# connect.net
KiCad netlist of a schematic drawn in EasyEDA Pro
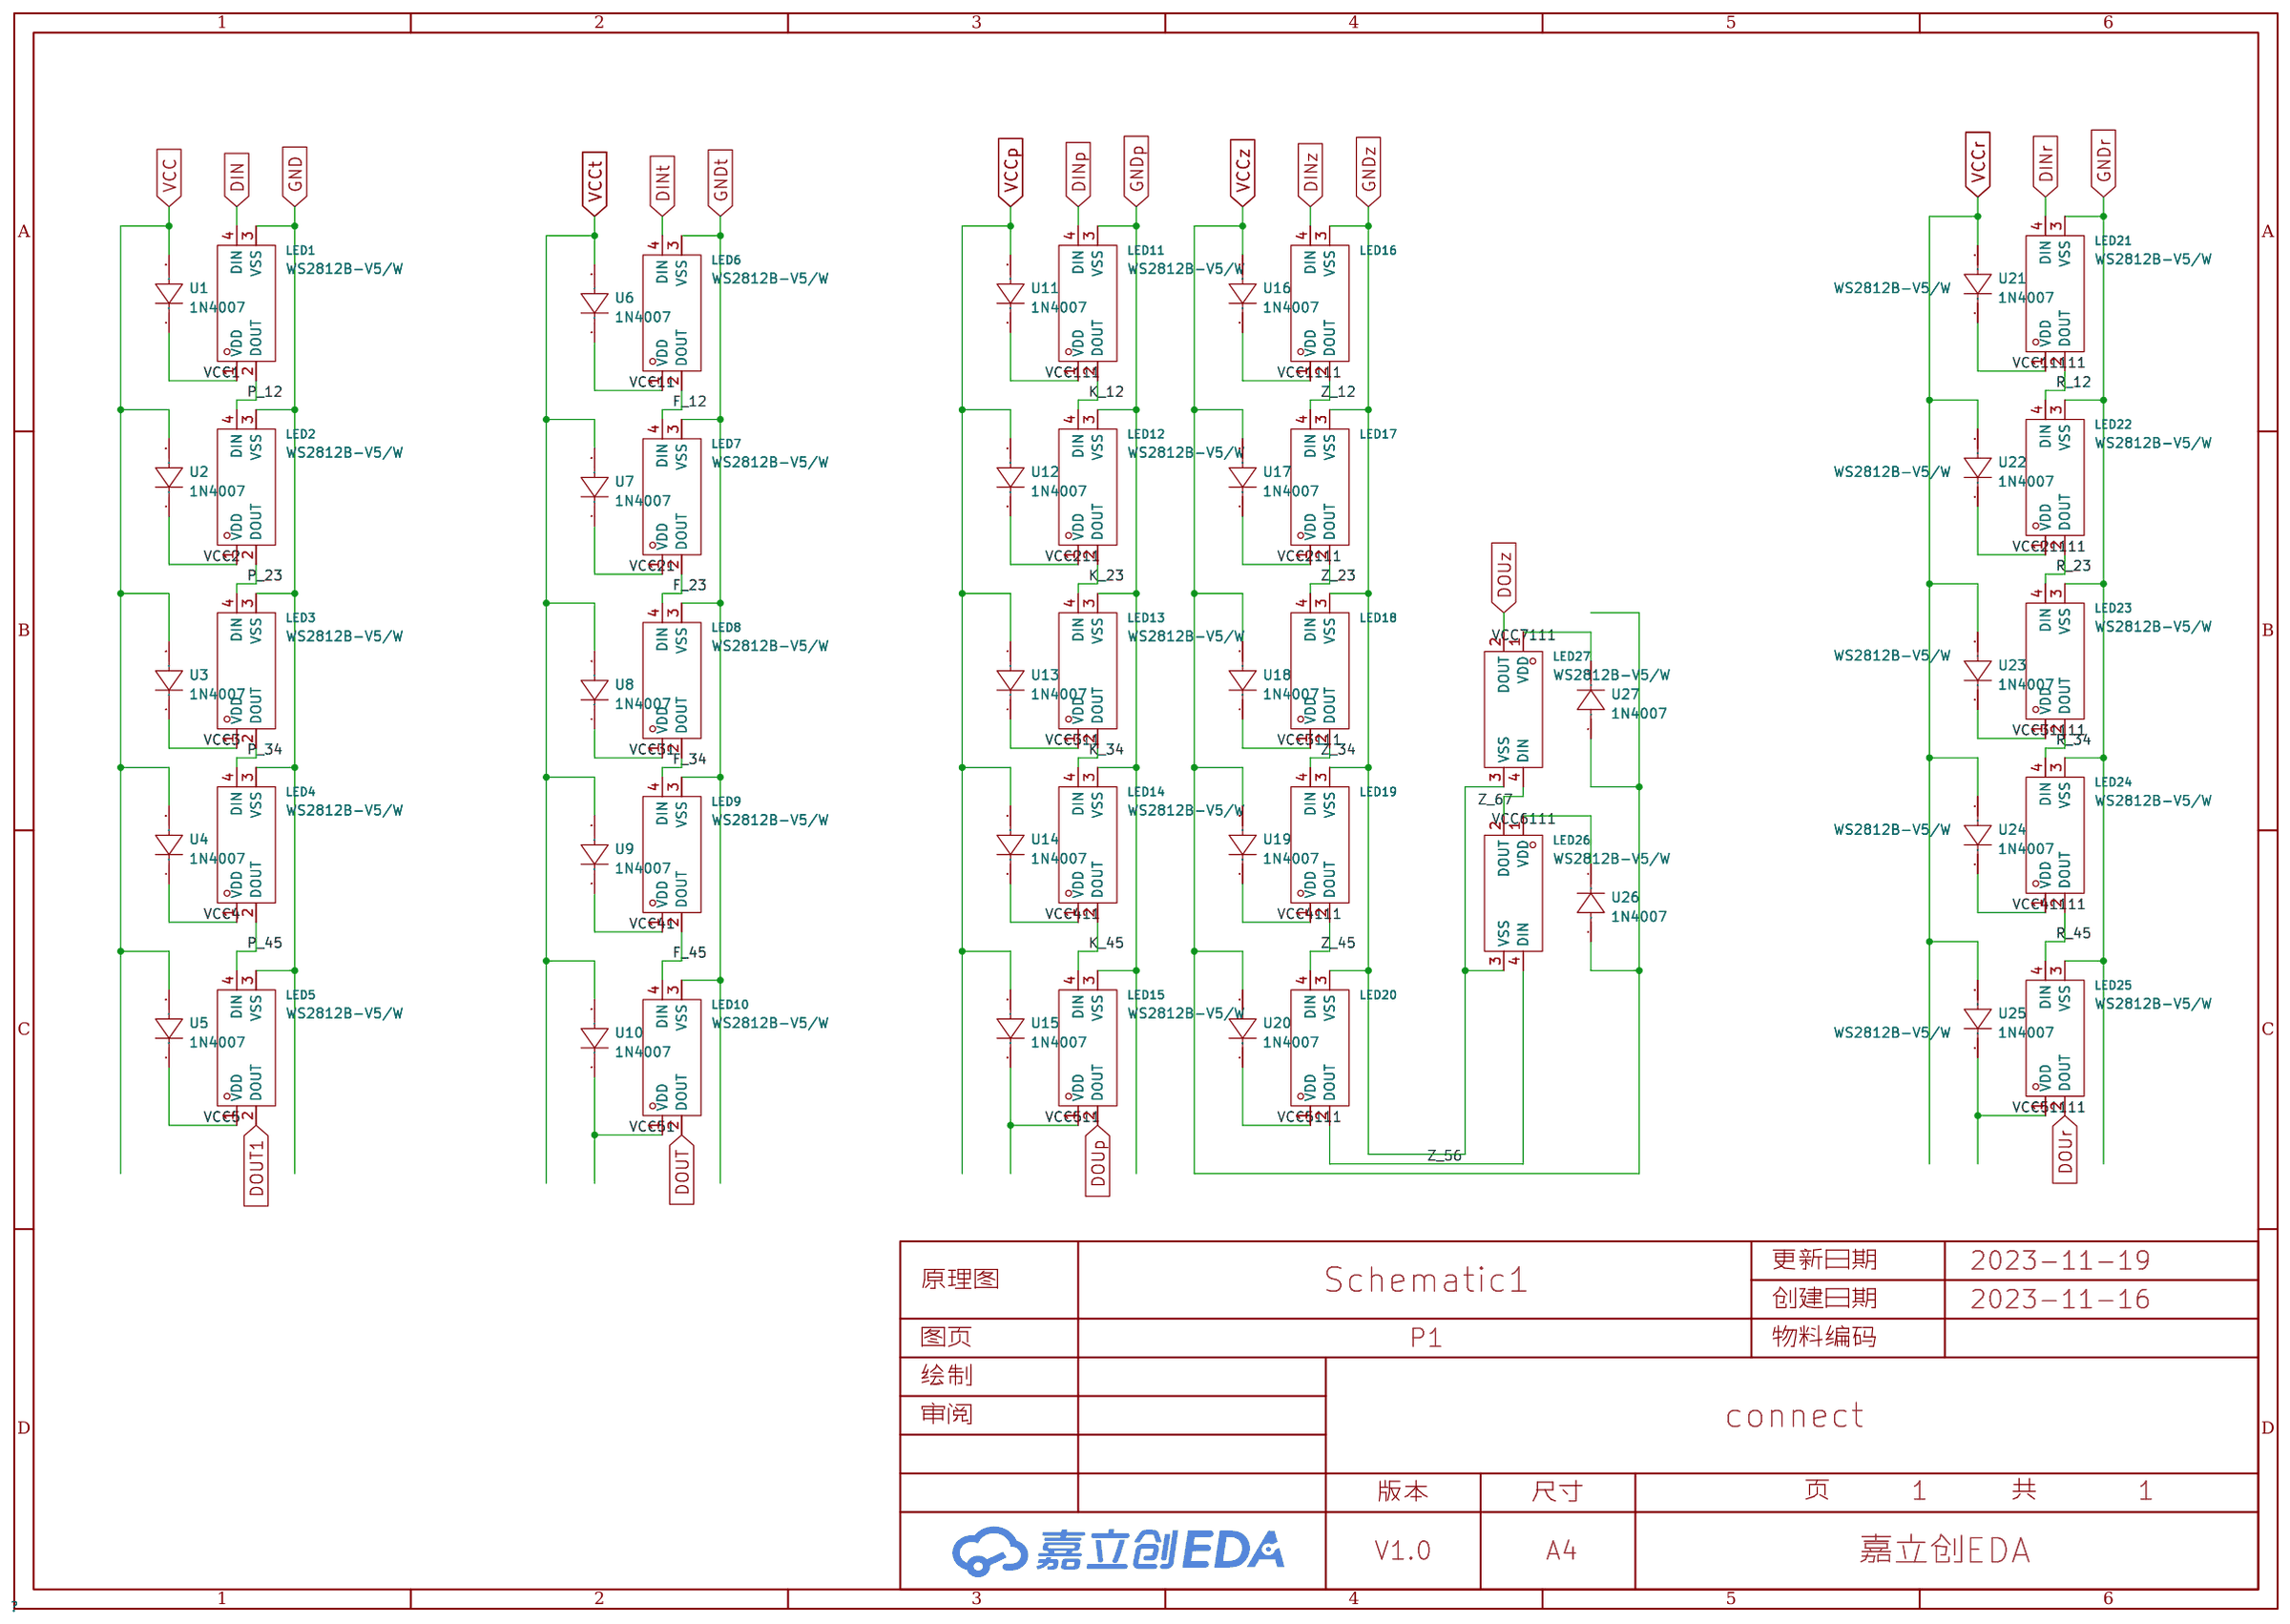
[diagram p0: schematic sheet]

(export (version "E")
  (design (tool "Eeschema 10.0.6"))
  (components
    (comp (ref "LED1")
      (value "WS2812B-V5/W")
      (footprint "easyedapro:LED-SMD_4P-L5.0-W5.0-TL-1")
      (description "无需外围元器件，有反接保护和过压保护，游乐设备，消费类电子，电竞领域，电脑周边及设备")
      (fields (field (name "Manufacturer") "worldsemi"))
      (libsource (lib "easyedapro") (part "WS2812B-V5/W"))
    )
    (comp (ref "LED2")
      (value "WS2812B-V5/W")
      (footprint "easyedapro:LED-SMD_4P-L5.0-W5.0-TL-1")
      (description "无需外围元器件，有反接保护和过压保护，游乐设备，消费类电子，电竞领域，电脑周边及设备")
      (fields (field (name "Manufacturer") "worldsemi"))
      (libsource (lib "easyedapro") (part "WS2812B-V5/W"))
    )
    (comp (ref "LED3")
      (value "WS2812B-V5/W")
      (footprint "easyedapro:LED-SMD_4P-L5.0-W5.0-TL-1")
      (description "无需外围元器件，有反接保护和过压保护，游乐设备，消费类电子，电竞领域，电脑周边及设备")
      (fields (field (name "Manufacturer") "worldsemi"))
      (libsource (lib "easyedapro") (part "WS2812B-V5/W"))
    )
    (comp (ref "LED4")
      (value "WS2812B-V5/W")
      (footprint "easyedapro:LED-SMD_4P-L5.0-W5.0-TL-1")
      (description "无需外围元器件，有反接保护和过压保护，游乐设备，消费类电子，电竞领域，电脑周边及设备")
      (fields (field (name "Manufacturer") "worldsemi"))
      (libsource (lib "easyedapro") (part "WS2812B-V5/W"))
    )
    (comp (ref "LED5")
      (value "WS2812B-V5/W")
      (footprint "easyedapro:LED-SMD_4P-L5.0-W5.0-TL-1")
      (description "无需外围元器件，有反接保护和过压保护，游乐设备，消费类电子，电竞领域，电脑周边及设备")
      (fields (field (name "Manufacturer") "worldsemi"))
      (libsource (lib "easyedapro") (part "WS2812B-V5/W"))
    )
    (comp (ref "LED6")
      (value "WS2812B-V5/W")
      (footprint "easyedapro:LED-SMD_4P-L5.0-W5.0-TL-1")
      (description "无需外围元器件，有反接保护和过压保护，游乐设备，消费类电子，电竞领域，电脑周边及设备")
      (fields (field (name "Manufacturer") "worldsemi"))
      (libsource (lib "easyedapro") (part "WS2812B-V5/W"))
    )
    (comp (ref "LED7")
      (value "WS2812B-V5/W")
      (footprint "easyedapro:LED-SMD_4P-L5.0-W5.0-TL-1")
      (description "无需外围元器件，有反接保护和过压保护，游乐设备，消费类电子，电竞领域，电脑周边及设备")
      (fields (field (name "Manufacturer") "worldsemi"))
      (libsource (lib "easyedapro") (part "WS2812B-V5/W"))
    )
    (comp (ref "LED8")
      (value "WS2812B-V5/W")
      (footprint "easyedapro:LED-SMD_4P-L5.0-W5.0-TL-1")
      (description "无需外围元器件，有反接保护和过压保护，游乐设备，消费类电子，电竞领域，电脑周边及设备")
      (fields (field (name "Manufacturer") "worldsemi"))
      (libsource (lib "easyedapro") (part "WS2812B-V5/W"))
    )
    (comp (ref "LED9")
      (value "WS2812B-V5/W")
      (footprint "easyedapro:LED-SMD_4P-L5.0-W5.0-TL-1")
      (description "无需外围元器件，有反接保护和过压保护，游乐设备，消费类电子，电竞领域，电脑周边及设备")
      (fields (field (name "Manufacturer") "worldsemi"))
      (libsource (lib "easyedapro") (part "WS2812B-V5/W"))
    )
    (comp (ref "LED10")
      (value "WS2812B-V5/W")
      (footprint "easyedapro:LED-SMD_4P-L5.0-W5.0-TL-1")
      (description "无需外围元器件，有反接保护和过压保护，游乐设备，消费类电子，电竞领域，电脑周边及设备")
      (fields (field (name "Manufacturer") "worldsemi"))
      (libsource (lib "easyedapro") (part "WS2812B-V5/W"))
    )
    (comp (ref "LED11")
      (value "WS2812B-V5/W")
      (footprint "easyedapro:LED-SMD_4P-L5.0-W5.0-TL-1")
      (description "无需外围元器件，有反接保护和过压保护，游乐设备，消费类电子，电竞领域，电脑周边及设备")
      (fields (field (name "Manufacturer") "worldsemi"))
      (libsource (lib "easyedapro") (part "WS2812B-V5/W"))
    )
    (comp (ref "LED12")
      (value "WS2812B-V5/W")
      (footprint "easyedapro:LED-SMD_4P-L5.0-W5.0-TL-1")
      (description "无需外围元器件，有反接保护和过压保护，游乐设备，消费类电子，电竞领域，电脑周边及设备")
      (fields (field (name "Manufacturer") "worldsemi"))
      (libsource (lib "easyedapro") (part "WS2812B-V5/W"))
    )
    (comp (ref "LED13")
      (value "WS2812B-V5/W")
      (footprint "easyedapro:LED-SMD_4P-L5.0-W5.0-TL-1")
      (description "无需外围元器件，有反接保护和过压保护，游乐设备，消费类电子，电竞领域，电脑周边及设备")
      (fields (field (name "Manufacturer") "worldsemi"))
      (libsource (lib "easyedapro") (part "WS2812B-V5/W"))
    )
    (comp (ref "LED14")
      (value "WS2812B-V5/W")
      (footprint "easyedapro:LED-SMD_4P-L5.0-W5.0-TL-1")
      (description "无需外围元器件，有反接保护和过压保护，游乐设备，消费类电子，电竞领域，电脑周边及设备")
      (fields (field (name "Manufacturer") "worldsemi"))
      (libsource (lib "easyedapro") (part "WS2812B-V5/W"))
    )
    (comp (ref "LED15")
      (value "WS2812B-V5/W")
      (footprint "easyedapro:LED-SMD_4P-L5.0-W5.0-TL-1")
      (description "无需外围元器件，有反接保护和过压保护，游乐设备，消费类电子，电竞领域，电脑周边及设备")
      (fields (field (name "Manufacturer") "worldsemi"))
      (libsource (lib "easyedapro") (part "WS2812B-V5/W"))
    )
    (comp (ref "LED16")
      (value "WS2812B-V5/W")
      (footprint "easyedapro:LED-SMD_4P-L5.0-W5.0-TL-1")
      (description "无需外围元器件，有反接保护和过压保护，游乐设备，消费类电子，电竞领域，电脑周边及设备")
      (fields (field (name "Manufacturer") "worldsemi"))
      (libsource (lib "easyedapro") (part "WS2812B-V5/W"))
    )
    (comp (ref "LED17")
      (value "WS2812B-V5/W")
      (footprint "easyedapro:LED-SMD_4P-L5.0-W5.0-TL-1")
      (description "无需外围元器件，有反接保护和过压保护，游乐设备，消费类电子，电竞领域，电脑周边及设备")
      (fields (field (name "Manufacturer") "worldsemi"))
      (libsource (lib "easyedapro") (part "WS2812B-V5/W"))
    )
    (comp (ref "LED18")
      (value "WS2812B-V5/W")
      (footprint "easyedapro:LED-SMD_4P-L5.0-W5.0-TL-1")
      (description "无需外围元器件，有反接保护和过压保护，游乐设备，消费类电子，电竞领域，电脑周边及设备")
      (fields (field (name "Manufacturer") "worldsemi"))
      (libsource (lib "easyedapro") (part "WS2812B-V5/W"))
    )
    (comp (ref "LED19")
      (value "WS2812B-V5/W")
      (footprint "easyedapro:LED-SMD_4P-L5.0-W5.0-TL-1")
      (description "无需外围元器件，有反接保护和过压保护，游乐设备，消费类电子，电竞领域，电脑周边及设备")
      (fields (field (name "Manufacturer") "worldsemi"))
      (libsource (lib "easyedapro") (part "WS2812B-V5/W"))
    )
    (comp (ref "LED20")
      (value "WS2812B-V5/W")
      (footprint "easyedapro:LED-SMD_4P-L5.0-W5.0-TL-1")
      (description "无需外围元器件，有反接保护和过压保护，游乐设备，消费类电子，电竞领域，电脑周边及设备")
      (fields (field (name "Manufacturer") "worldsemi"))
      (libsource (lib "easyedapro") (part "WS2812B-V5/W"))
    )
    (comp (ref "LED21")
      (value "WS2812B-V5/W")
      (footprint "easyedapro:LED-SMD_4P-L5.0-W5.0-TL-1")
      (description "无需外围元器件，有反接保护和过压保护，游乐设备，消费类电子，电竞领域，电脑周边及设备")
      (fields (field (name "Manufacturer") "worldsemi"))
      (libsource (lib "easyedapro") (part "WS2812B-V5/W"))
    )
    (comp (ref "LED22")
      (value "WS2812B-V5/W")
      (footprint "easyedapro:LED-SMD_4P-L5.0-W5.0-TL-1")
      (description "无需外围元器件，有反接保护和过压保护，游乐设备，消费类电子，电竞领域，电脑周边及设备")
      (fields (field (name "Manufacturer") "worldsemi"))
      (libsource (lib "easyedapro") (part "WS2812B-V5/W"))
    )
    (comp (ref "LED23")
      (value "WS2812B-V5/W")
      (footprint "easyedapro:LED-SMD_4P-L5.0-W5.0-TL-1")
      (description "无需外围元器件，有反接保护和过压保护，游乐设备，消费类电子，电竞领域，电脑周边及设备")
      (fields (field (name "Manufacturer") "worldsemi"))
      (libsource (lib "easyedapro") (part "WS2812B-V5/W"))
    )
    (comp (ref "LED24")
      (value "WS2812B-V5/W")
      (footprint "easyedapro:LED-SMD_4P-L5.0-W5.0-TL-1")
      (description "无需外围元器件，有反接保护和过压保护，游乐设备，消费类电子，电竞领域，电脑周边及设备")
      (fields (field (name "Manufacturer") "worldsemi"))
      (libsource (lib "easyedapro") (part "WS2812B-V5/W"))
    )
    (comp (ref "LED25")
      (value "WS2812B-V5/W")
      (footprint "easyedapro:LED-SMD_4P-L5.0-W5.0-TL-1")
      (description "无需外围元器件，有反接保护和过压保护，游乐设备，消费类电子，电竞领域，电脑周边及设备")
      (fields (field (name "Manufacturer") "worldsemi"))
      (libsource (lib "easyedapro") (part "WS2812B-V5/W"))
    )
    (comp (ref "LED26")
      (value "WS2812B-V5/W")
      (footprint "easyedapro:LED-SMD_4P-L5.0-W5.0-TL-1")
      (description "无需外围元器件，有反接保护和过压保护，游乐设备，消费类电子，电竞领域，电脑周边及设备")
      (fields (field (name "Manufacturer") "worldsemi"))
      (libsource (lib "easyedapro") (part "WS2812B-V5/W"))
    )
    (comp (ref "LED27")
      (value "WS2812B-V5/W")
      (footprint "easyedapro:LED-SMD_4P-L5.0-W5.0-TL-1")
      (description "无需外围元器件，有反接保护和过压保护，游乐设备，消费类电子，电竞领域，电脑周边及设备")
      (fields (field (name "Manufacturer") "worldsemi"))
      (libsource (lib "easyedapro") (part "WS2812B-V5/W"))
    )
    (comp (ref "U1")
      (value "1N4007")
      (footprint "easyedapro:SMA_L4.3-W2.6-LS5.1-RD")
      (libsource (lib "easyedapro") (part "1N4007_C9900004759"))
    )
    (comp (ref "U2")
      (value "1N4007")
      (footprint "easyedapro:SMA_L4.3-W2.6-LS5.1-RD")
      (libsource (lib "easyedapro") (part "1N4007_C9900004759"))
    )
    (comp (ref "U3")
      (value "1N4007")
      (footprint "easyedapro:SMA_L4.3-W2.6-LS5.1-RD")
      (libsource (lib "easyedapro") (part "1N4007_C9900004759"))
    )
    (comp (ref "U4")
      (value "1N4007")
      (footprint "easyedapro:SMA_L4.3-W2.6-LS5.1-RD")
      (libsource (lib "easyedapro") (part "1N4007_C9900004759"))
    )
    (comp (ref "U5")
      (value "1N4007")
      (footprint "easyedapro:SMA_L4.3-W2.6-LS5.1-RD")
      (libsource (lib "easyedapro") (part "1N4007_C9900004759"))
    )
    (comp (ref "U6")
      (value "1N4007")
      (footprint "easyedapro:SMA_L4.3-W2.6-LS5.1-RD")
      (libsource (lib "easyedapro") (part "1N4007_C9900004759"))
    )
    (comp (ref "U7")
      (value "1N4007")
      (footprint "easyedapro:SMA_L4.3-W2.6-LS5.1-RD")
      (libsource (lib "easyedapro") (part "1N4007_C9900004759"))
    )
    (comp (ref "U8")
      (value "1N4007")
      (footprint "easyedapro:SMA_L4.3-W2.6-LS5.1-RD")
      (libsource (lib "easyedapro") (part "1N4007_C9900004759"))
    )
    (comp (ref "U9")
      (value "1N4007")
      (footprint "easyedapro:SMA_L4.3-W2.6-LS5.1-RD")
      (libsource (lib "easyedapro") (part "1N4007_C9900004759"))
    )
    (comp (ref "U10")
      (value "1N4007")
      (footprint "easyedapro:SMA_L4.3-W2.6-LS5.1-RD")
      (libsource (lib "easyedapro") (part "1N4007_C9900004759"))
    )
    (comp (ref "U11")
      (value "1N4007")
      (footprint "easyedapro:SMA_L4.3-W2.6-LS5.1-RD")
      (libsource (lib "easyedapro") (part "1N4007_C9900004759"))
    )
    (comp (ref "U12")
      (value "1N4007")
      (footprint "easyedapro:SMA_L4.3-W2.6-LS5.1-RD")
      (libsource (lib "easyedapro") (part "1N4007_C9900004759"))
    )
    (comp (ref "U13")
      (value "1N4007")
      (footprint "easyedapro:SMA_L4.3-W2.6-LS5.1-RD")
      (libsource (lib "easyedapro") (part "1N4007_C9900004759"))
    )
    (comp (ref "U14")
      (value "1N4007")
      (footprint "easyedapro:SMA_L4.3-W2.6-LS5.1-RD")
      (libsource (lib "easyedapro") (part "1N4007_C9900004759"))
    )
    (comp (ref "U15")
      (value "1N4007")
      (footprint "easyedapro:SMA_L4.3-W2.6-LS5.1-RD")
      (libsource (lib "easyedapro") (part "1N4007_C9900004759"))
    )
    (comp (ref "U16")
      (value "1N4007")
      (footprint "easyedapro:SMA_L4.3-W2.6-LS5.1-RD")
      (libsource (lib "easyedapro") (part "1N4007_C9900004759"))
    )
    (comp (ref "U17")
      (value "1N4007")
      (footprint "easyedapro:SMA_L4.3-W2.6-LS5.1-RD")
      (libsource (lib "easyedapro") (part "1N4007_C9900004759"))
    )
    (comp (ref "U18")
      (value "1N4007")
      (footprint "easyedapro:SMA_L4.3-W2.6-LS5.1-RD")
      (libsource (lib "easyedapro") (part "1N4007_C9900004759"))
    )
    (comp (ref "U19")
      (value "1N4007")
      (footprint "easyedapro:SMA_L4.3-W2.6-LS5.1-RD")
      (libsource (lib "easyedapro") (part "1N4007_C9900004759"))
    )
    (comp (ref "U20")
      (value "1N4007")
      (footprint "easyedapro:SMA_L4.3-W2.6-LS5.1-RD")
      (libsource (lib "easyedapro") (part "1N4007_C9900004759"))
    )
    (comp (ref "U21")
      (value "1N4007")
      (footprint "easyedapro:SMA_L4.3-W2.6-LS5.1-RD")
      (libsource (lib "easyedapro") (part "1N4007_C9900004759"))
    )
    (comp (ref "U22")
      (value "1N4007")
      (footprint "easyedapro:SMA_L4.3-W2.6-LS5.1-RD")
      (libsource (lib "easyedapro") (part "1N4007_C9900004759"))
    )
    (comp (ref "U23")
      (value "1N4007")
      (footprint "easyedapro:SMA_L4.3-W2.6-LS5.1-RD")
      (libsource (lib "easyedapro") (part "1N4007_C9900004759"))
    )
    (comp (ref "U24")
      (value "1N4007")
      (footprint "easyedapro:SMA_L4.3-W2.6-LS5.1-RD")
      (libsource (lib "easyedapro") (part "1N4007_C9900004759"))
    )
    (comp (ref "U25")
      (value "1N4007")
      (footprint "easyedapro:SMA_L4.3-W2.6-LS5.1-RD")
      (libsource (lib "easyedapro") (part "1N4007_C9900004759"))
    )
    (comp (ref "U26")
      (value "1N4007")
      (footprint "easyedapro:SMA_L4.3-W2.6-LS5.1-RD")
      (libsource (lib "easyedapro") (part "1N4007_C9900004759"))
    )
    (comp (ref "U27")
      (value "1N4007")
      (footprint "easyedapro:SMA_L4.3-W2.6-LS5.1-RD")
      (libsource (lib "easyedapro") (part "1N4007_C9900004759"))
    )
  )
  (nets
    (net (code "1") (name "/F_12") (class "Default")
      (node (ref "LED6") (pin "2") (pinfunction "DOUT_2") (pintype "input"))
      (node (ref "LED7") (pin "4") (pinfunction "DIN_4") (pintype "input"))
    )
    (net (code "2") (name "/F_23") (class "Default")
      (node (ref "LED7") (pin "2") (pinfunction "DOUT_2") (pintype "input"))
      (node (ref "LED8") (pin "4") (pinfunction "DIN_4") (pintype "input"))
    )
    (net (code "3") (name "/F_34") (class "Default")
      (node (ref "LED8") (pin "2") (pinfunction "DOUT_2") (pintype "input"))
      (node (ref "LED9") (pin "4") (pinfunction "DIN_4") (pintype "input"))
    )
    (net (code "4") (name "/F_45") (class "Default")
      (node (ref "LED10") (pin "4") (pinfunction "DIN_4") (pintype "input"))
      (node (ref "LED9") (pin "2") (pinfunction "DOUT_2") (pintype "input"))
    )
    (net (code "5") (name "/K_12") (class "Default")
      (node (ref "LED11") (pin "2") (pinfunction "DOUT_2") (pintype "input"))
      (node (ref "LED12") (pin "4") (pinfunction "DIN_4") (pintype "input"))
    )
    (net (code "6") (name "/K_23") (class "Default")
      (node (ref "LED12") (pin "2") (pinfunction "DOUT_2") (pintype "input"))
      (node (ref "LED13") (pin "4") (pinfunction "DIN_4") (pintype "input"))
    )
    (net (code "7") (name "/K_34") (class "Default")
      (node (ref "LED13") (pin "2") (pinfunction "DOUT_2") (pintype "input"))
      (node (ref "LED14") (pin "4") (pinfunction "DIN_4") (pintype "input"))
    )
    (net (code "8") (name "/K_45") (class "Default")
      (node (ref "LED14") (pin "2") (pinfunction "DOUT_2") (pintype "input"))
      (node (ref "LED15") (pin "4") (pinfunction "DIN_4") (pintype "input"))
    )
    (net (code "9") (name "/P_12") (class "Default")
      (node (ref "LED1") (pin "2") (pinfunction "DOUT_2") (pintype "input"))
      (node (ref "LED2") (pin "4") (pinfunction "DIN_4") (pintype "input"))
    )
    (net (code "10") (name "/P_23") (class "Default")
      (node (ref "LED2") (pin "2") (pinfunction "DOUT_2") (pintype "input"))
      (node (ref "LED3") (pin "4") (pinfunction "DIN_4") (pintype "input"))
    )
    (net (code "11") (name "/P_34") (class "Default")
      (node (ref "LED3") (pin "2") (pinfunction "DOUT_2") (pintype "input"))
      (node (ref "LED4") (pin "4") (pinfunction "DIN_4") (pintype "input"))
    )
    (net (code "12") (name "/P_45") (class "Default")
      (node (ref "LED4") (pin "2") (pinfunction "DOUT_2") (pintype "input"))
      (node (ref "LED5") (pin "4") (pinfunction "DIN_4") (pintype "input"))
    )
    (net (code "13") (name "/R_12") (class "Default")
      (node (ref "LED21") (pin "2") (pinfunction "DOUT_2") (pintype "input"))
      (node (ref "LED22") (pin "4") (pinfunction "DIN_4") (pintype "input"))
    )
    (net (code "14") (name "/R_23") (class "Default")
      (node (ref "LED22") (pin "2") (pinfunction "DOUT_2") (pintype "input"))
      (node (ref "LED23") (pin "4") (pinfunction "DIN_4") (pintype "input"))
    )
    (net (code "15") (name "/R_34") (class "Default")
      (node (ref "LED23") (pin "2") (pinfunction "DOUT_2") (pintype "input"))
      (node (ref "LED24") (pin "4") (pinfunction "DIN_4") (pintype "input"))
    )
    (net (code "16") (name "/R_45") (class "Default")
      (node (ref "LED24") (pin "2") (pinfunction "DOUT_2") (pintype "input"))
      (node (ref "LED25") (pin "4") (pinfunction "DIN_4") (pintype "input"))
    )
    (net (code "17") (name "/VCC1") (class "Default")
      (node (ref "LED1") (pin "1") (pinfunction "VDD_1") (pintype "input"))
      (node (ref "U1") (pin "1") (pinfunction "K_1") (pintype "input"))
    )
    (net (code "18") (name "/VCC2") (class "Default")
      (node (ref "LED2") (pin "1") (pinfunction "VDD_1") (pintype "input"))
      (node (ref "U2") (pin "1") (pinfunction "K_1") (pintype "input"))
    )
    (net (code "19") (name "/VCC3") (class "Default")
      (node (ref "LED3") (pin "1") (pinfunction "VDD_1") (pintype "input"))
      (node (ref "U3") (pin "1") (pinfunction "K_1") (pintype "input"))
    )
    (net (code "20") (name "/VCC4") (class "Default")
      (node (ref "LED4") (pin "1") (pinfunction "VDD_1") (pintype "input"))
      (node (ref "U4") (pin "1") (pinfunction "K_1") (pintype "input"))
    )
    (net (code "21") (name "/VCC5") (class "Default")
      (node (ref "LED5") (pin "1") (pinfunction "VDD_1") (pintype "input"))
      (node (ref "U5") (pin "1") (pinfunction "K_1") (pintype "input"))
    )
    (net (code "22") (name "/VCC11") (class "Default")
      (node (ref "LED6") (pin "1") (pinfunction "VDD_1") (pintype "input"))
      (node (ref "U6") (pin "1") (pinfunction "K_1") (pintype "input"))
    )
    (net (code "23") (name "/VCC21") (class "Default")
      (node (ref "LED7") (pin "1") (pinfunction "VDD_1") (pintype "input"))
      (node (ref "U7") (pin "1") (pinfunction "K_1") (pintype "input"))
    )
    (net (code "24") (name "/VCC31") (class "Default")
      (node (ref "LED8") (pin "1") (pinfunction "VDD_1") (pintype "input"))
      (node (ref "U8") (pin "1") (pinfunction "K_1") (pintype "input"))
    )
    (net (code "25") (name "/VCC41") (class "Default")
      (node (ref "LED9") (pin "1") (pinfunction "VDD_1") (pintype "input"))
      (node (ref "U9") (pin "1") (pinfunction "K_1") (pintype "input"))
    )
    (net (code "26") (name "/VCC51") (class "Default")
      (node (ref "LED10") (pin "1") (pinfunction "VDD_1") (pintype "input"))
      (node (ref "U10") (pin "1") (pinfunction "K_1") (pintype "input"))
    )
    (net (code "27") (name "/VCC111") (class "Default")
      (node (ref "LED11") (pin "1") (pinfunction "VDD_1") (pintype "input"))
      (node (ref "U11") (pin "1") (pinfunction "K_1") (pintype "input"))
    )
    (net (code "28") (name "/VCC211") (class "Default")
      (node (ref "LED12") (pin "1") (pinfunction "VDD_1") (pintype "input"))
      (node (ref "U12") (pin "1") (pinfunction "K_1") (pintype "input"))
    )
    (net (code "29") (name "/VCC311") (class "Default")
      (node (ref "LED13") (pin "1") (pinfunction "VDD_1") (pintype "input"))
      (node (ref "U13") (pin "1") (pinfunction "K_1") (pintype "input"))
    )
    (net (code "30") (name "/VCC411") (class "Default")
      (node (ref "LED14") (pin "1") (pinfunction "VDD_1") (pintype "input"))
      (node (ref "U14") (pin "1") (pinfunction "K_1") (pintype "input"))
    )
    (net (code "31") (name "/VCC511") (class "Default")
      (node (ref "LED15") (pin "1") (pinfunction "VDD_1") (pintype "input"))
      (node (ref "U15") (pin "1") (pinfunction "K_1") (pintype "input"))
    )
    (net (code "32") (name "/VCC1111") (class "Default")
      (node (ref "LED16") (pin "1") (pinfunction "VDD_1") (pintype "input"))
      (node (ref "U16") (pin "1") (pinfunction "K_1") (pintype "input"))
    )
    (net (code "33") (name "/VCC2111") (class "Default")
      (node (ref "LED17") (pin "1") (pinfunction "VDD_1") (pintype "input"))
      (node (ref "U17") (pin "1") (pinfunction "K_1") (pintype "input"))
    )
    (net (code "34") (name "/VCC3111") (class "Default")
      (node (ref "LED18") (pin "1") (pinfunction "VDD_1") (pintype "input"))
      (node (ref "U18") (pin "1") (pinfunction "K_1") (pintype "input"))
    )
    (net (code "35") (name "/VCC4111") (class "Default")
      (node (ref "LED19") (pin "1") (pinfunction "VDD_1") (pintype "input"))
      (node (ref "U19") (pin "1") (pinfunction "K_1") (pintype "input"))
    )
    (net (code "36") (name "/VCC5111") (class "Default")
      (node (ref "LED20") (pin "1") (pinfunction "VDD_1") (pintype "input"))
      (node (ref "U20") (pin "1") (pinfunction "K_1") (pintype "input"))
    )
    (net (code "37") (name "/VCC6111") (class "Default")
      (node (ref "LED26") (pin "1") (pinfunction "VDD_1") (pintype "input"))
      (node (ref "U26") (pin "1") (pinfunction "K_1") (pintype "input"))
    )
    (net (code "38") (name "/VCC7111") (class "Default")
      (node (ref "LED27") (pin "1") (pinfunction "VDD_1") (pintype "input"))
      (node (ref "U27") (pin "1") (pinfunction "K_1") (pintype "input"))
    )
    (net (code "39") (name "/VCC11111") (class "Default")
      (node (ref "LED21") (pin "1") (pinfunction "VDD_1") (pintype "input"))
      (node (ref "U21") (pin "1") (pinfunction "K_1") (pintype "input"))
    )
    (net (code "40") (name "/VCC21111") (class "Default")
      (node (ref "LED22") (pin "1") (pinfunction "VDD_1") (pintype "input"))
      (node (ref "U22") (pin "1") (pinfunction "K_1") (pintype "input"))
    )
    (net (code "41") (name "/VCC31111") (class "Default")
      (node (ref "LED23") (pin "1") (pinfunction "VDD_1") (pintype "input"))
      (node (ref "U23") (pin "1") (pinfunction "K_1") (pintype "input"))
    )
    (net (code "42") (name "/VCC41111") (class "Default")
      (node (ref "LED24") (pin "1") (pinfunction "VDD_1") (pintype "input"))
      (node (ref "U24") (pin "1") (pinfunction "K_1") (pintype "input"))
    )
    (net (code "43") (name "/VCC51111") (class "Default")
      (node (ref "LED25") (pin "1") (pinfunction "VDD_1") (pintype "input"))
      (node (ref "U25") (pin "1") (pinfunction "K_1") (pintype "input"))
    )
    (net (code "44") (name "/Z_12") (class "Default")
      (node (ref "LED16") (pin "2") (pinfunction "DOUT_2") (pintype "input"))
      (node (ref "LED17") (pin "4") (pinfunction "DIN_4") (pintype "input"))
    )
    (net (code "45") (name "/Z_23") (class "Default")
      (node (ref "LED17") (pin "2") (pinfunction "DOUT_2") (pintype "input"))
      (node (ref "LED18") (pin "4") (pinfunction "DIN_4") (pintype "input"))
    )
    (net (code "46") (name "/Z_34") (class "Default")
      (node (ref "LED18") (pin "2") (pinfunction "DOUT_2") (pintype "input"))
      (node (ref "LED19") (pin "4") (pinfunction "DIN_4") (pintype "input"))
    )
    (net (code "47") (name "/Z_45") (class "Default")
      (node (ref "LED19") (pin "2") (pinfunction "DOUT_2") (pintype "input"))
      (node (ref "LED20") (pin "4") (pinfunction "DIN_4") (pintype "input"))
    )
    (net (code "48") (name "/Z_56") (class "Default")
      (node (ref "LED20") (pin "2") (pinfunction "DOUT_2") (pintype "input"))
      (node (ref "LED26") (pin "4") (pinfunction "DIN_4") (pintype "input"))
    )
    (net (code "49") (name "/Z_67") (class "Default")
      (node (ref "LED26") (pin "2") (pinfunction "DOUT_2") (pintype "input"))
      (node (ref "LED27") (pin "4") (pinfunction "DIN_4") (pintype "input"))
    )
    (net (code "50") (name "DIN") (class "Default")
      (node (ref "LED1") (pin "4") (pinfunction "DIN_4") (pintype "input"))
    )
    (net (code "51") (name "DINp") (class "Default")
      (node (ref "LED11") (pin "4") (pinfunction "DIN_4") (pintype "input"))
    )
    (net (code "52") (name "DINr") (class "Default")
      (node (ref "LED21") (pin "4") (pinfunction "DIN_4") (pintype "input"))
    )
    (net (code "53") (name "DINt") (class "Default")
      (node (ref "LED6") (pin "4") (pinfunction "DIN_4") (pintype "input"))
    )
    (net (code "54") (name "DINz") (class "Default")
      (node (ref "LED16") (pin "4") (pinfunction "DIN_4") (pintype "input"))
    )
    (net (code "55") (name "DOUT") (class "Default")
      (node (ref "LED10") (pin "2") (pinfunction "DOUT_2") (pintype "input"))
    )
    (net (code "56") (name "DOUT1") (class "Default")
      (node (ref "LED5") (pin "2") (pinfunction "DOUT_2") (pintype "input"))
    )
    (net (code "57") (name "DOUp") (class "Default")
      (node (ref "LED15") (pin "2") (pinfunction "DOUT_2") (pintype "input"))
    )
    (net (code "58") (name "DOUr") (class "Default")
      (node (ref "LED25") (pin "2") (pinfunction "DOUT_2") (pintype "input"))
    )
    (net (code "59") (name "DOUz") (class "Default")
      (node (ref "LED27") (pin "2") (pinfunction "DOUT_2") (pintype "input"))
    )
    (net (code "60") (name "GND") (class "Default")
      (node (ref "LED1") (pin "3") (pinfunction "VSS_3") (pintype "input"))
      (node (ref "LED2") (pin "3") (pinfunction "VSS_3") (pintype "input"))
      (node (ref "LED3") (pin "3") (pinfunction "VSS_3") (pintype "input"))
      (node (ref "LED4") (pin "3") (pinfunction "VSS_3") (pintype "input"))
      (node (ref "LED5") (pin "3") (pinfunction "VSS_3") (pintype "input"))
    )
    (net (code "61") (name "GNDp") (class "Default")
      (node (ref "LED11") (pin "3") (pinfunction "VSS_3") (pintype "input"))
      (node (ref "LED12") (pin "3") (pinfunction "VSS_3") (pintype "input"))
      (node (ref "LED13") (pin "3") (pinfunction "VSS_3") (pintype "input"))
      (node (ref "LED14") (pin "3") (pinfunction "VSS_3") (pintype "input"))
      (node (ref "LED15") (pin "3") (pinfunction "VSS_3") (pintype "input"))
    )
    (net (code "62") (name "GNDr") (class "Default")
      (node (ref "LED21") (pin "3") (pinfunction "VSS_3") (pintype "input"))
      (node (ref "LED22") (pin "3") (pinfunction "VSS_3") (pintype "input"))
      (node (ref "LED23") (pin "3") (pinfunction "VSS_3") (pintype "input"))
      (node (ref "LED24") (pin "3") (pinfunction "VSS_3") (pintype "input"))
      (node (ref "LED25") (pin "3") (pinfunction "VSS_3") (pintype "input"))
    )
    (net (code "63") (name "GNDt") (class "Default")
      (node (ref "LED10") (pin "3") (pinfunction "VSS_3") (pintype "input"))
      (node (ref "LED6") (pin "3") (pinfunction "VSS_3") (pintype "input"))
      (node (ref "LED7") (pin "3") (pinfunction "VSS_3") (pintype "input"))
      (node (ref "LED8") (pin "3") (pinfunction "VSS_3") (pintype "input"))
      (node (ref "LED9") (pin "3") (pinfunction "VSS_3") (pintype "input"))
    )
    (net (code "64") (name "GNDz") (class "Default")
      (node (ref "LED16") (pin "3") (pinfunction "VSS_3") (pintype "input"))
      (node (ref "LED17") (pin "3") (pinfunction "VSS_3") (pintype "input"))
      (node (ref "LED18") (pin "3") (pinfunction "VSS_3") (pintype "input"))
      (node (ref "LED19") (pin "3") (pinfunction "VSS_3") (pintype "input"))
      (node (ref "LED20") (pin "3") (pinfunction "VSS_3") (pintype "input"))
      (node (ref "LED26") (pin "3") (pinfunction "VSS_3") (pintype "input"))
      (node (ref "LED27") (pin "3") (pinfunction "VSS_3") (pintype "input"))
    )
    (net (code "65") (name "VCC") (class "Default")
      (node (ref "U1") (pin "2") (pinfunction "A_2") (pintype "input"))
      (node (ref "U2") (pin "2") (pinfunction "A_2") (pintype "input"))
      (node (ref "U3") (pin "2") (pinfunction "A_2") (pintype "input"))
      (node (ref "U4") (pin "2") (pinfunction "A_2") (pintype "input"))
      (node (ref "U5") (pin "2") (pinfunction "A_2") (pintype "input"))
    )
    (net (code "66") (name "VCCp") (class "Default")
      (node (ref "U11") (pin "2") (pinfunction "A_2") (pintype "input"))
      (node (ref "U12") (pin "2") (pinfunction "A_2") (pintype "input"))
      (node (ref "U13") (pin "2") (pinfunction "A_2") (pintype "input"))
      (node (ref "U14") (pin "2") (pinfunction "A_2") (pintype "input"))
      (node (ref "U15") (pin "2") (pinfunction "A_2") (pintype "input"))
    )
    (net (code "67") (name "VCCr") (class "Default")
      (node (ref "U21") (pin "2") (pinfunction "A_2") (pintype "input"))
      (node (ref "U22") (pin "2") (pinfunction "A_2") (pintype "input"))
      (node (ref "U23") (pin "2") (pinfunction "A_2") (pintype "input"))
      (node (ref "U24") (pin "2") (pinfunction "A_2") (pintype "input"))
      (node (ref "U25") (pin "2") (pinfunction "A_2") (pintype "input"))
    )
    (net (code "68") (name "VCCt") (class "Default")
      (node (ref "U10") (pin "2") (pinfunction "A_2") (pintype "input"))
      (node (ref "U6") (pin "2") (pinfunction "A_2") (pintype "input"))
      (node (ref "U7") (pin "2") (pinfunction "A_2") (pintype "input"))
      (node (ref "U8") (pin "2") (pinfunction "A_2") (pintype "input"))
      (node (ref "U9") (pin "2") (pinfunction "A_2") (pintype "input"))
    )
    (net (code "69") (name "VCCz") (class "Default")
      (node (ref "U16") (pin "2") (pinfunction "A_2") (pintype "input"))
      (node (ref "U17") (pin "2") (pinfunction "A_2") (pintype "input"))
      (node (ref "U18") (pin "2") (pinfunction "A_2") (pintype "input"))
      (node (ref "U19") (pin "2") (pinfunction "A_2") (pintype "input"))
      (node (ref "U20") (pin "2") (pinfunction "A_2") (pintype "input"))
      (node (ref "U26") (pin "2") (pinfunction "A_2") (pintype "input"))
      (node (ref "U27") (pin "2") (pinfunction "A_2") (pintype "input"))
    )
  )
)
